# sbox.net
KiCad netlist of a schematic drawn in EAGLE
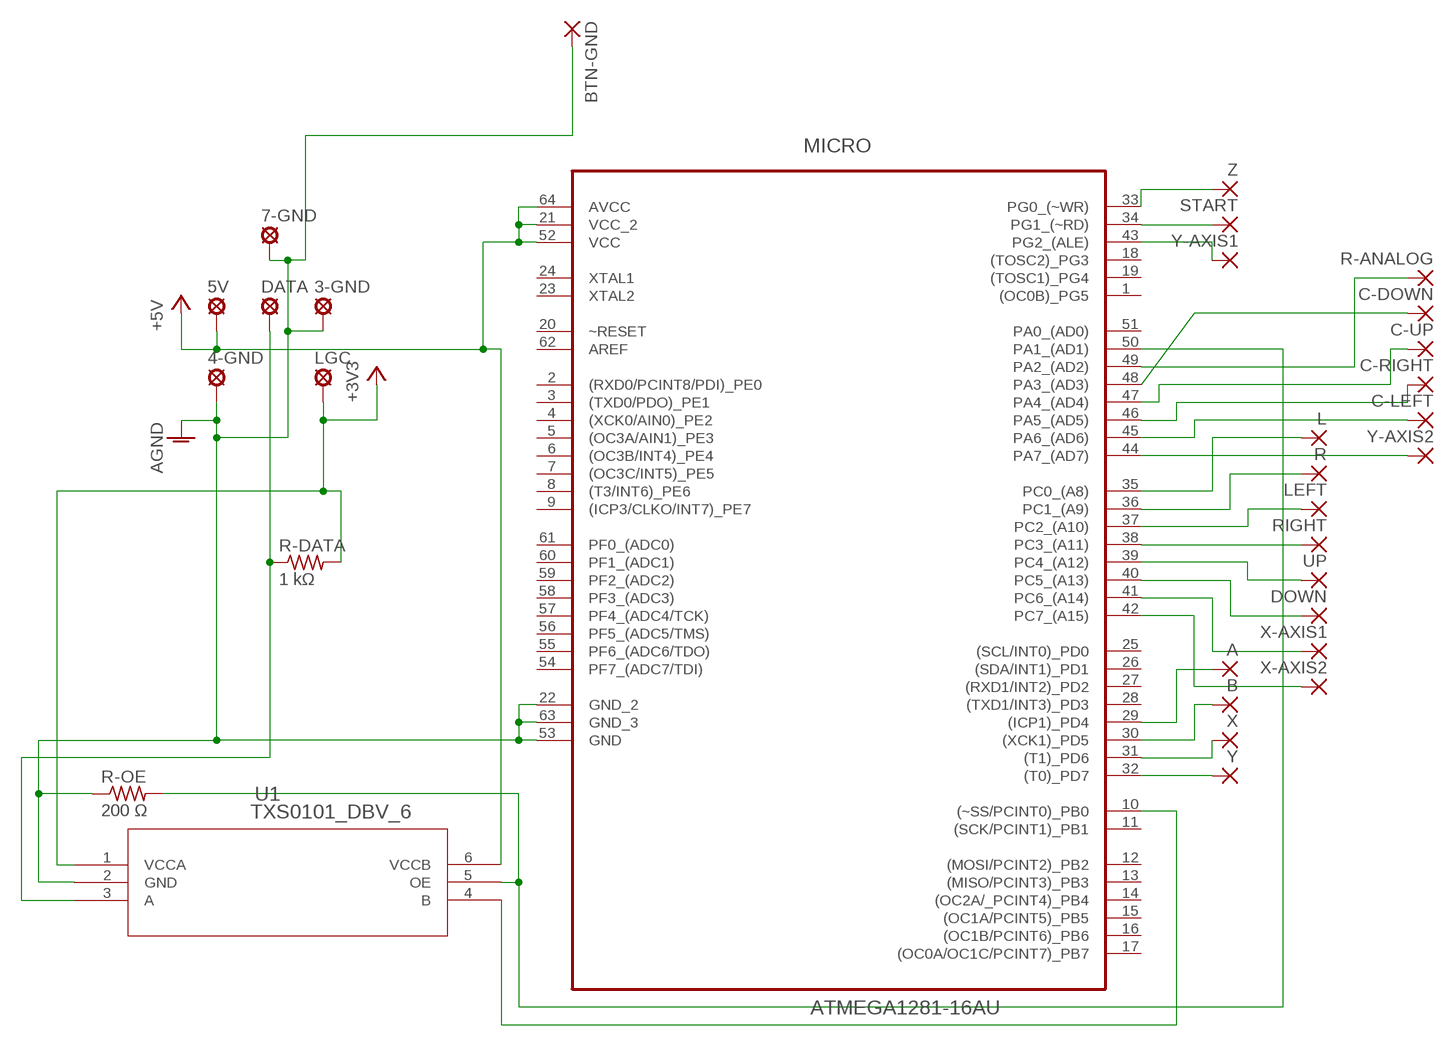
[diagram p0: schematic, sheet 1]

(export (version "E")
  (design (tool "Eeschema 10.0.6"))
  (components
    (comp (ref "3-GND")
      (value "LSP10")
      (footprint "eagle-import:LSP10")
      (libsource (lib "eagle-import") (part "LSP10"))
    )
    (comp (ref "4-GND")
      (value "LSP10")
      (footprint "eagle-import:LSP10")
      (libsource (lib "eagle-import") (part "LSP10"))
    )
    (comp (ref "5V")
      (value "LSP10")
      (footprint "eagle-import:LSP10")
      (libsource (lib "eagle-import") (part "LSP10"))
    )
    (comp (ref "7-GND")
      (value "LSP10")
      (footprint "eagle-import:LSP10")
      (libsource (lib "eagle-import") (part "LSP10"))
    )
    (comp (ref "A")
      (value "1,6/0,8")
      (footprint "eagle-import:1,6_0,8")
      (libsource (lib "eagle-import") (part "1,6/0,8"))
    )
    (comp (ref "B")
      (value "1,6/0,8")
      (footprint "eagle-import:1,6_0,8")
      (libsource (lib "eagle-import") (part "1,6/0,8"))
    )
    (comp (ref "BTN-GND")
      (value "1,6/0,8")
      (footprint "eagle-import:1,6_0,8")
      (libsource (lib "eagle-import") (part "1,6/0,8"))
    )
    (comp (ref "C-DOWN")
      (value "1,6/0,8")
      (footprint "eagle-import:1,6_0,8")
      (libsource (lib "eagle-import") (part "1,6/0,8"))
    )
    (comp (ref "C-LEFT")
      (value "1,6/0,8")
      (footprint "eagle-import:1,6_0,8")
      (libsource (lib "eagle-import") (part "1,6/0,8"))
    )
    (comp (ref "C-RIGHT")
      (value "1,6/0,8")
      (footprint "eagle-import:1,6_0,8")
      (libsource (lib "eagle-import") (part "1,6/0,8"))
    )
    (comp (ref "C-UP")
      (value "1,6/0,8")
      (footprint "eagle-import:1,6_0,8")
      (libsource (lib "eagle-import") (part "1,6/0,8"))
    )
    (comp (ref "DATA")
      (value "LSP10")
      (footprint "eagle-import:LSP10")
      (libsource (lib "eagle-import") (part "LSP10"))
    )
    (comp (ref "DOWN")
      (value "1,6/0,8")
      (footprint "eagle-import:1,6_0,8")
      (libsource (lib "eagle-import") (part "1,6/0,8"))
    )
    (comp (ref "L")
      (value "1,6/0,8")
      (footprint "eagle-import:1,6_0,8")
      (libsource (lib "eagle-import") (part "1,6/0,8"))
    )
    (comp (ref "LEFT")
      (value "1,6/0,8")
      (footprint "eagle-import:1,6_0,8")
      (libsource (lib "eagle-import") (part "1,6/0,8"))
    )
    (comp (ref "LGC")
      (value "LSP10")
      (footprint "eagle-import:LSP10")
      (libsource (lib "eagle-import") (part "LSP10"))
    )
    (comp (ref "MICRO")
      (value "ATMEGA1281-16AU")
      (footprint "eagle-import:QFP80P1600X1600X120-64N")
      (libsource (lib "eagle-import") (part "ATMEGA1281-16AU"))
    )
    (comp (ref "R")
      (value "1,6/0,8")
      (footprint "eagle-import:1,6_0,8")
      (libsource (lib "eagle-import") (part "1,6/0,8"))
    )
    (comp (ref "R-ANALOG")
      (value "1,6/0,8")
      (footprint "eagle-import:1,6_0,8")
      (libsource (lib "eagle-import") (part "1,6/0,8"))
    )
    (comp (ref "R-DATA")
      (value "1 kΩ")
      (footprint "eagle-import:0207_12")
      (libsource (lib "eagle-import") (part "R-US_0207/12"))
    )
    (comp (ref "R-OE")
      (value "200 Ω")
      (footprint "eagle-import:0207_12")
      (libsource (lib "eagle-import") (part "R-US_0207/12"))
    )
    (comp (ref "RIGHT")
      (value "1,6/0,8")
      (footprint "eagle-import:1,6_0,8")
      (libsource (lib "eagle-import") (part "1,6/0,8"))
    )
    (comp (ref "START")
      (value "1,6/0,8")
      (footprint "eagle-import:1,6_0,8")
      (libsource (lib "eagle-import") (part "1,6/0,8"))
    )
    (comp (ref "U1")
      (value "TXS0101_DBV_6")
      (footprint "eagle-import:DBV6")
      (fields
        (field (name "GENERIC_PART_NUMBER") "TXS0101")
        (field (name "MANUFACTURER") "Texas Instruments")
        (field (name "MANUFACTURER_PART_NUMBER") "txs0101_dbv_6")
      )
      (libsource (lib "eagle-import") (part "TXS0101_DBV_6"))
    )
    (comp (ref "UP")
      (value "1,6/0,8")
      (footprint "eagle-import:1,6_0,8")
      (libsource (lib "eagle-import") (part "1,6/0,8"))
    )
    (comp (ref "X")
      (value "1,6/0,8")
      (footprint "eagle-import:1,6_0,8")
      (libsource (lib "eagle-import") (part "1,6/0,8"))
    )
    (comp (ref "X-AXIS1")
      (value "1,6/0,8")
      (footprint "eagle-import:1,6_0,8")
      (libsource (lib "eagle-import") (part "1,6/0,8"))
    )
    (comp (ref "X-AXIS2")
      (value "1,6/0,8")
      (footprint "eagle-import:1,6_0,8")
      (libsource (lib "eagle-import") (part "1,6/0,8"))
    )
    (comp (ref "Y")
      (value "1,6/0,8")
      (footprint "eagle-import:1,6_0,8")
      (libsource (lib "eagle-import") (part "1,6/0,8"))
    )
    (comp (ref "Y-AXIS1")
      (value "1,6/0,8")
      (footprint "eagle-import:1,6_0,8")
      (libsource (lib "eagle-import") (part "1,6/0,8"))
    )
    (comp (ref "Y-AXIS2")
      (value "1,6/0,8")
      (footprint "eagle-import:1,6_0,8")
      (libsource (lib "eagle-import") (part "1,6/0,8"))
    )
    (comp (ref "Z")
      (value "1,6/0,8")
      (footprint "eagle-import:1,6_0,8")
      (libsource (lib "eagle-import") (part "1,6/0,8"))
    )
  )
  (nets
    (net (code "1") (name "+3V3") (class "Default")
      (node (ref "LGC") (pin "MP") (pinfunction "MP_MP") (pintype "passive"))
      (node (ref "R-DATA") (pin "2") (pinfunction "2_2") (pintype "passive"))
      (node (ref "U1") (pin "1") (pinfunction "VCCA_1") (pintype "power_in"))
    )
    (net (code "2") (name "+5V") (class "Default")
      (node (ref "5V") (pin "MP") (pinfunction "MP_MP") (pintype "passive"))
      (node (ref "MICRO") (pin "21") (pinfunction "VCC_2_21") (pintype "power_in"))
      (node (ref "MICRO") (pin "52") (pinfunction "VCC_52") (pintype "power_in"))
      (node (ref "MICRO") (pin "64") (pinfunction "AVCC_64") (pintype "power_in"))
      (node (ref "U1") (pin "6") (pinfunction "VCCB_6") (pintype "power_in"))
    )
    (net (code "3") (name "AGND") (class "Default")
      (node (ref "3-GND") (pin "MP") (pinfunction "MP_MP") (pintype "passive"))
      (node (ref "4-GND") (pin "MP") (pinfunction "MP_MP") (pintype "passive"))
      (node (ref "7-GND") (pin "MP") (pinfunction "MP_MP") (pintype "passive"))
      (node (ref "BTN-GND") (pin "1") (pinfunction "P_1") (pintype "passive"))
      (node (ref "MICRO") (pin "22") (pinfunction "GND_2_22") (pintype "passive"))
      (node (ref "MICRO") (pin "53") (pinfunction "GND_53") (pintype "passive"))
      (node (ref "MICRO") (pin "63") (pinfunction "GND_3_63") (pintype "passive"))
      (node (ref "R-OE") (pin "1") (pinfunction "1_1") (pintype "passive"))
      (node (ref "U1") (pin "2") (pinfunction "GND_2") (pintype "power_in"))
    )
    (net (code "4") (name "Net-(A-P)") (class "Default")
      (node (ref "A") (pin "1") (pinfunction "P_1") (pintype "passive"))
      (node (ref "MICRO") (pin "29") (pinfunction "(ICP1)_PD4_29") (pintype "bidirectional"))
    )
    (net (code "5") (name "Net-(B-P)") (class "Default")
      (node (ref "B") (pin "1") (pinfunction "P_1") (pintype "passive"))
      (node (ref "MICRO") (pin "30") (pinfunction "(XCK1)_PD5_30") (pintype "bidirectional"))
    )
    (net (code "6") (name "Net-(C-DOWN-P)") (class "Default")
      (node (ref "C-DOWN") (pin "1") (pinfunction "P_1") (pintype "passive"))
      (node (ref "MICRO") (pin "48") (pinfunction "PA3_(AD3)_48") (pintype "bidirectional"))
    )
    (net (code "7") (name "Net-(C-LEFT-P)") (class "Default")
      (node (ref "C-LEFT") (pin "1") (pinfunction "P_1") (pintype "passive"))
      (node (ref "MICRO") (pin "45") (pinfunction "PA6_(AD6)_45") (pintype "bidirectional"))
    )
    (net (code "8") (name "Net-(C-RIGHT-P)") (class "Default")
      (node (ref "C-RIGHT") (pin "1") (pinfunction "P_1") (pintype "passive"))
      (node (ref "MICRO") (pin "46") (pinfunction "PA5_(AD5)_46") (pintype "bidirectional"))
    )
    (net (code "9") (name "Net-(C-UP-P)") (class "Default")
      (node (ref "C-UP") (pin "1") (pinfunction "P_1") (pintype "passive"))
      (node (ref "MICRO") (pin "47") (pinfunction "PA4_(AD4)_47") (pintype "bidirectional"))
    )
    (net (code "10") (name "Net-(DOWN-P)") (class "Default")
      (node (ref "DOWN") (pin "1") (pinfunction "P_1") (pintype "passive"))
      (node (ref "MICRO") (pin "40") (pinfunction "PC5_(A13)_40") (pintype "bidirectional"))
    )
    (net (code "11") (name "Net-(L-P)") (class "Default")
      (node (ref "L") (pin "1") (pinfunction "P_1") (pintype "passive"))
      (node (ref "MICRO") (pin "35") (pinfunction "PC0_(A8)_35") (pintype "bidirectional"))
    )
    (net (code "12") (name "Net-(LEFT-P)") (class "Default")
      (node (ref "LEFT") (pin "1") (pinfunction "P_1") (pintype "passive"))
      (node (ref "MICRO") (pin "37") (pinfunction "PC2_(A10)_37") (pintype "bidirectional"))
    )
    (net (code "13") (name "Net-(MICRO-(T0)_PD7)") (class "Default")
      (node (ref "MICRO") (pin "32") (pinfunction "(T0)_PD7_32") (pintype "bidirectional"))
      (node (ref "Y") (pin "1") (pinfunction "P_1") (pintype "passive"))
    )
    (net (code "14") (name "Net-(MICRO-(T1)_PD6)") (class "Default")
      (node (ref "MICRO") (pin "31") (pinfunction "(T1)_PD6_31") (pintype "bidirectional"))
      (node (ref "X") (pin "1") (pinfunction "P_1") (pintype "passive"))
    )
    (net (code "15") (name "Net-(MICRO-(~{SS{slash}PCINT0})_PB0)") (class "Default")
      (node (ref "MICRO") (pin "10") (pinfunction "(~{SS/PCINT0})_PB0_10") (pintype "bidirectional"))
      (node (ref "U1") (pin "4") (pinfunction "B_4") (pintype "bidirectional"))
    )
    (net (code "16") (name "Net-(MICRO-PA1_(AD1))") (class "Default")
      (node (ref "MICRO") (pin "50") (pinfunction "PA1_(AD1)_50") (pintype "bidirectional"))
      (node (ref "R-OE") (pin "2") (pinfunction "2_2") (pintype "passive"))
      (node (ref "U1") (pin "5") (pinfunction "OE_5") (pintype "output"))
    )
    (net (code "17") (name "Net-(MICRO-PA2_(AD2))") (class "Default")
      (node (ref "MICRO") (pin "49") (pinfunction "PA2_(AD2)_49") (pintype "bidirectional"))
      (node (ref "R-ANALOG") (pin "1") (pinfunction "P_1") (pintype "passive"))
    )
    (net (code "18") (name "Net-(MICRO-PA7_(AD7))") (class "Default")
      (node (ref "MICRO") (pin "44") (pinfunction "PA7_(AD7)_44") (pintype "bidirectional"))
      (node (ref "Y-AXIS2") (pin "1") (pinfunction "P_1") (pintype "passive"))
    )
    (net (code "19") (name "Net-(MICRO-PC1_(A9))") (class "Default")
      (node (ref "MICRO") (pin "36") (pinfunction "PC1_(A9)_36") (pintype "bidirectional"))
      (node (ref "R") (pin "1") (pinfunction "P_1") (pintype "passive"))
    )
    (net (code "20") (name "Net-(MICRO-PC3_(A11))") (class "Default")
      (node (ref "MICRO") (pin "38") (pinfunction "PC3_(A11)_38") (pintype "bidirectional"))
      (node (ref "RIGHT") (pin "1") (pinfunction "P_1") (pintype "passive"))
    )
    (net (code "21") (name "Net-(MICRO-PC4_(A12))") (class "Default")
      (node (ref "MICRO") (pin "39") (pinfunction "PC4_(A12)_39") (pintype "bidirectional"))
      (node (ref "UP") (pin "1") (pinfunction "P_1") (pintype "passive"))
    )
    (net (code "22") (name "Net-(MICRO-PC6_(A14))") (class "Default")
      (node (ref "MICRO") (pin "41") (pinfunction "PC6_(A14)_41") (pintype "bidirectional"))
      (node (ref "X-AXIS1") (pin "1") (pinfunction "P_1") (pintype "passive"))
    )
    (net (code "23") (name "Net-(MICRO-PC7_(A15))") (class "Default")
      (node (ref "MICRO") (pin "42") (pinfunction "PC7_(A15)_42") (pintype "bidirectional"))
      (node (ref "X-AXIS2") (pin "1") (pinfunction "P_1") (pintype "passive"))
    )
    (net (code "24") (name "Net-(MICRO-PG0_(~{WR}))") (class "Default")
      (node (ref "MICRO") (pin "33") (pinfunction "PG0_(~{WR})_33") (pintype "bidirectional"))
      (node (ref "Z") (pin "1") (pinfunction "P_1") (pintype "passive"))
    )
    (net (code "25") (name "Net-(MICRO-PG1_(~{RD}))") (class "Default")
      (node (ref "MICRO") (pin "34") (pinfunction "PG1_(~{RD})_34") (pintype "bidirectional"))
      (node (ref "START") (pin "1") (pinfunction "P_1") (pintype "passive"))
    )
    (net (code "26") (name "Net-(MICRO-PG2_(ALE))") (class "Default")
      (node (ref "MICRO") (pin "43") (pinfunction "PG2_(ALE)_43") (pintype "bidirectional"))
      (node (ref "Y-AXIS1") (pin "1") (pinfunction "P_1") (pintype "passive"))
    )
    (net (code "27") (name "Net-(U1-A)") (class "Default")
      (node (ref "DATA") (pin "MP") (pinfunction "MP_MP") (pintype "passive"))
      (node (ref "R-DATA") (pin "1") (pinfunction "1_1") (pintype "passive"))
      (node (ref "U1") (pin "3") (pinfunction "A_3") (pintype "bidirectional"))
    )
    (net (code "28") (name "unconnected-(MICRO-(ICP3{slash}CLKO{slash}INT7)_PE7-Pad9)") (class "Default")
      (node (ref "MICRO") (pin "9") (pinfunction "(ICP3/CLKO/INT7)_PE7_9") (pintype "bidirectional"))
    )
    (net (code "29") (name "unconnected-(MICRO-(MISO{slash}PCINT3)_PB3-Pad13)") (class "Default")
      (node (ref "MICRO") (pin "13") (pinfunction "(MISO/PCINT3)_PB3_13") (pintype "bidirectional"))
    )
    (net (code "30") (name "unconnected-(MICRO-(MOSI{slash}PCINT2)_PB2-Pad12)") (class "Default")
      (node (ref "MICRO") (pin "12") (pinfunction "(MOSI/PCINT2)_PB2_12") (pintype "bidirectional"))
    )
    (net (code "31") (name "unconnected-(MICRO-(OC0A{slash}OC1C{slash}PCINT7)_PB7-Pad17)") (class "Default")
      (node (ref "MICRO") (pin "17") (pinfunction "(OC0A/OC1C/PCINT7)_PB7_17") (pintype "bidirectional"))
    )
    (net (code "32") (name "unconnected-(MICRO-(OC0B)_PG5-Pad1)") (class "Default")
      (node (ref "MICRO") (pin "1") (pinfunction "(OC0B)_PG5_1") (pintype "bidirectional"))
    )
    (net (code "33") (name "unconnected-(MICRO-(OC1A{slash}PCINT5)_PB5-Pad15)") (class "Default")
      (node (ref "MICRO") (pin "15") (pinfunction "(OC1A/PCINT5)_PB5_15") (pintype "bidirectional"))
    )
    (net (code "34") (name "unconnected-(MICRO-(OC1B{slash}PCINT6)_PB6-Pad16)") (class "Default")
      (node (ref "MICRO") (pin "16") (pinfunction "(OC1B/PCINT6)_PB6_16") (pintype "bidirectional"))
    )
    (net (code "35") (name "unconnected-(MICRO-(OC2A{slash}_PCINT4)_PB4-Pad14)") (class "Default")
      (node (ref "MICRO") (pin "14") (pinfunction "(OC2A/_PCINT4)_PB4_14") (pintype "bidirectional"))
    )
    (net (code "36") (name "unconnected-(MICRO-(OC3A{slash}AIN1)_PE3-Pad5)") (class "Default")
      (node (ref "MICRO") (pin "5") (pinfunction "(OC3A/AIN1)_PE3_5") (pintype "bidirectional"))
    )
    (net (code "37") (name "unconnected-(MICRO-(OC3B{slash}INT4)_PE4-Pad6)") (class "Default")
      (node (ref "MICRO") (pin "6") (pinfunction "(OC3B/INT4)_PE4_6") (pintype "bidirectional"))
    )
    (net (code "38") (name "unconnected-(MICRO-(OC3C{slash}INT5)_PE5-Pad7)") (class "Default")
      (node (ref "MICRO") (pin "7") (pinfunction "(OC3C/INT5)_PE5_7") (pintype "bidirectional"))
    )
    (net (code "39") (name "unconnected-(MICRO-(RXD0{slash}PCINT8{slash}PDI)_PE0-Pad2)") (class "Default")
      (node (ref "MICRO") (pin "2") (pinfunction "(RXD0/PCINT8/PDI)_PE0_2") (pintype "bidirectional"))
    )
    (net (code "40") (name "unconnected-(MICRO-(RXD1{slash}INT2)_PD2-Pad27)") (class "Default")
      (node (ref "MICRO") (pin "27") (pinfunction "(RXD1/INT2)_PD2_27") (pintype "bidirectional"))
    )
    (net (code "41") (name "unconnected-(MICRO-(SCK{slash}PCINT1)_PB1-Pad11)") (class "Default")
      (node (ref "MICRO") (pin "11") (pinfunction "(SCK/PCINT1)_PB1_11") (pintype "bidirectional"))
    )
    (net (code "42") (name "unconnected-(MICRO-(SCL{slash}INT0)_PD0-Pad25)") (class "Default")
      (node (ref "MICRO") (pin "25") (pinfunction "(SCL/INT0)_PD0_25") (pintype "bidirectional"))
    )
    (net (code "43") (name "unconnected-(MICRO-(SDA{slash}INT1)_PD1-Pad26)") (class "Default")
      (node (ref "MICRO") (pin "26") (pinfunction "(SDA/INT1)_PD1_26") (pintype "bidirectional"))
    )
    (net (code "44") (name "unconnected-(MICRO-(T3{slash}INT6)_PE6-Pad8)") (class "Default")
      (node (ref "MICRO") (pin "8") (pinfunction "(T3/INT6)_PE6_8") (pintype "bidirectional"))
    )
    (net (code "45") (name "unconnected-(MICRO-(TOSC1)_PG4-Pad19)") (class "Default")
      (node (ref "MICRO") (pin "19") (pinfunction "(TOSC1)_PG4_19") (pintype "bidirectional"))
    )
    (net (code "46") (name "unconnected-(MICRO-(TOSC2)_PG3-Pad18)") (class "Default")
      (node (ref "MICRO") (pin "18") (pinfunction "(TOSC2)_PG3_18") (pintype "bidirectional"))
    )
    (net (code "47") (name "unconnected-(MICRO-(TXD0{slash}PDO)_PE1-Pad3)") (class "Default")
      (node (ref "MICRO") (pin "3") (pinfunction "(TXD0/PDO)_PE1_3") (pintype "bidirectional"))
    )
    (net (code "48") (name "unconnected-(MICRO-(TXD1{slash}INT3)_PD3-Pad28)") (class "Default")
      (node (ref "MICRO") (pin "28") (pinfunction "(TXD1/INT3)_PD3_28") (pintype "bidirectional"))
    )
    (net (code "49") (name "unconnected-(MICRO-(XCK0{slash}AIN0)_PE2-Pad4)") (class "Default")
      (node (ref "MICRO") (pin "4") (pinfunction "(XCK0/AIN0)_PE2_4") (pintype "bidirectional"))
    )
    (net (code "50") (name "unconnected-(MICRO-AREF-Pad62)") (class "Default")
      (node (ref "MICRO") (pin "62") (pinfunction "AREF_62") (pintype "input"))
    )
    (net (code "51") (name "unconnected-(MICRO-PA0_(AD0)-Pad51)") (class "Default")
      (node (ref "MICRO") (pin "51") (pinfunction "PA0_(AD0)_51") (pintype "bidirectional"))
    )
    (net (code "52") (name "unconnected-(MICRO-PF0_(ADC0)-Pad61)") (class "Default")
      (node (ref "MICRO") (pin "61") (pinfunction "PF0_(ADC0)_61") (pintype "bidirectional"))
    )
    (net (code "53") (name "unconnected-(MICRO-PF1_(ADC1)-Pad60)") (class "Default")
      (node (ref "MICRO") (pin "60") (pinfunction "PF1_(ADC1)_60") (pintype "bidirectional"))
    )
    (net (code "54") (name "unconnected-(MICRO-PF2_(ADC2)-Pad59)") (class "Default")
      (node (ref "MICRO") (pin "59") (pinfunction "PF2_(ADC2)_59") (pintype "bidirectional"))
    )
    (net (code "55") (name "unconnected-(MICRO-PF3_(ADC3)-Pad58)") (class "Default")
      (node (ref "MICRO") (pin "58") (pinfunction "PF3_(ADC3)_58") (pintype "bidirectional"))
    )
    (net (code "56") (name "unconnected-(MICRO-PF4_(ADC4{slash}TCK)-Pad57)") (class "Default")
      (node (ref "MICRO") (pin "57") (pinfunction "PF4_(ADC4/TCK)_57") (pintype "bidirectional"))
    )
    (net (code "57") (name "unconnected-(MICRO-PF5_(ADC5{slash}TMS)-Pad56)") (class "Default")
      (node (ref "MICRO") (pin "56") (pinfunction "PF5_(ADC5/TMS)_56") (pintype "bidirectional"))
    )
    (net (code "58") (name "unconnected-(MICRO-PF6_(ADC6{slash}TDO)-Pad55)") (class "Default")
      (node (ref "MICRO") (pin "55") (pinfunction "PF6_(ADC6/TDO)_55") (pintype "bidirectional"))
    )
    (net (code "59") (name "unconnected-(MICRO-PF7_(ADC7{slash}TDI)-Pad54)") (class "Default")
      (node (ref "MICRO") (pin "54") (pinfunction "PF7_(ADC7/TDI)_54") (pintype "bidirectional"))
    )
    (net (code "60") (name "unconnected-(MICRO-XTAL1-Pad24)") (class "Default")
      (node (ref "MICRO") (pin "24") (pinfunction "XTAL1_24") (pintype "input"))
    )
    (net (code "61") (name "unconnected-(MICRO-XTAL2-Pad23)") (class "Default")
      (node (ref "MICRO") (pin "23") (pinfunction "XTAL2_23") (pintype "input"))
    )
    (net (code "62") (name "unconnected-(MICRO-~{RESET}-Pad20)") (class "Default")
      (node (ref "MICRO") (pin "20") (pinfunction "~{RESET}_20") (pintype "input"))
    )
  )
)
